# NMEA0183Breakout-ISO-4_3.net
KiCad netlist of a schematic drawn in EAGLE
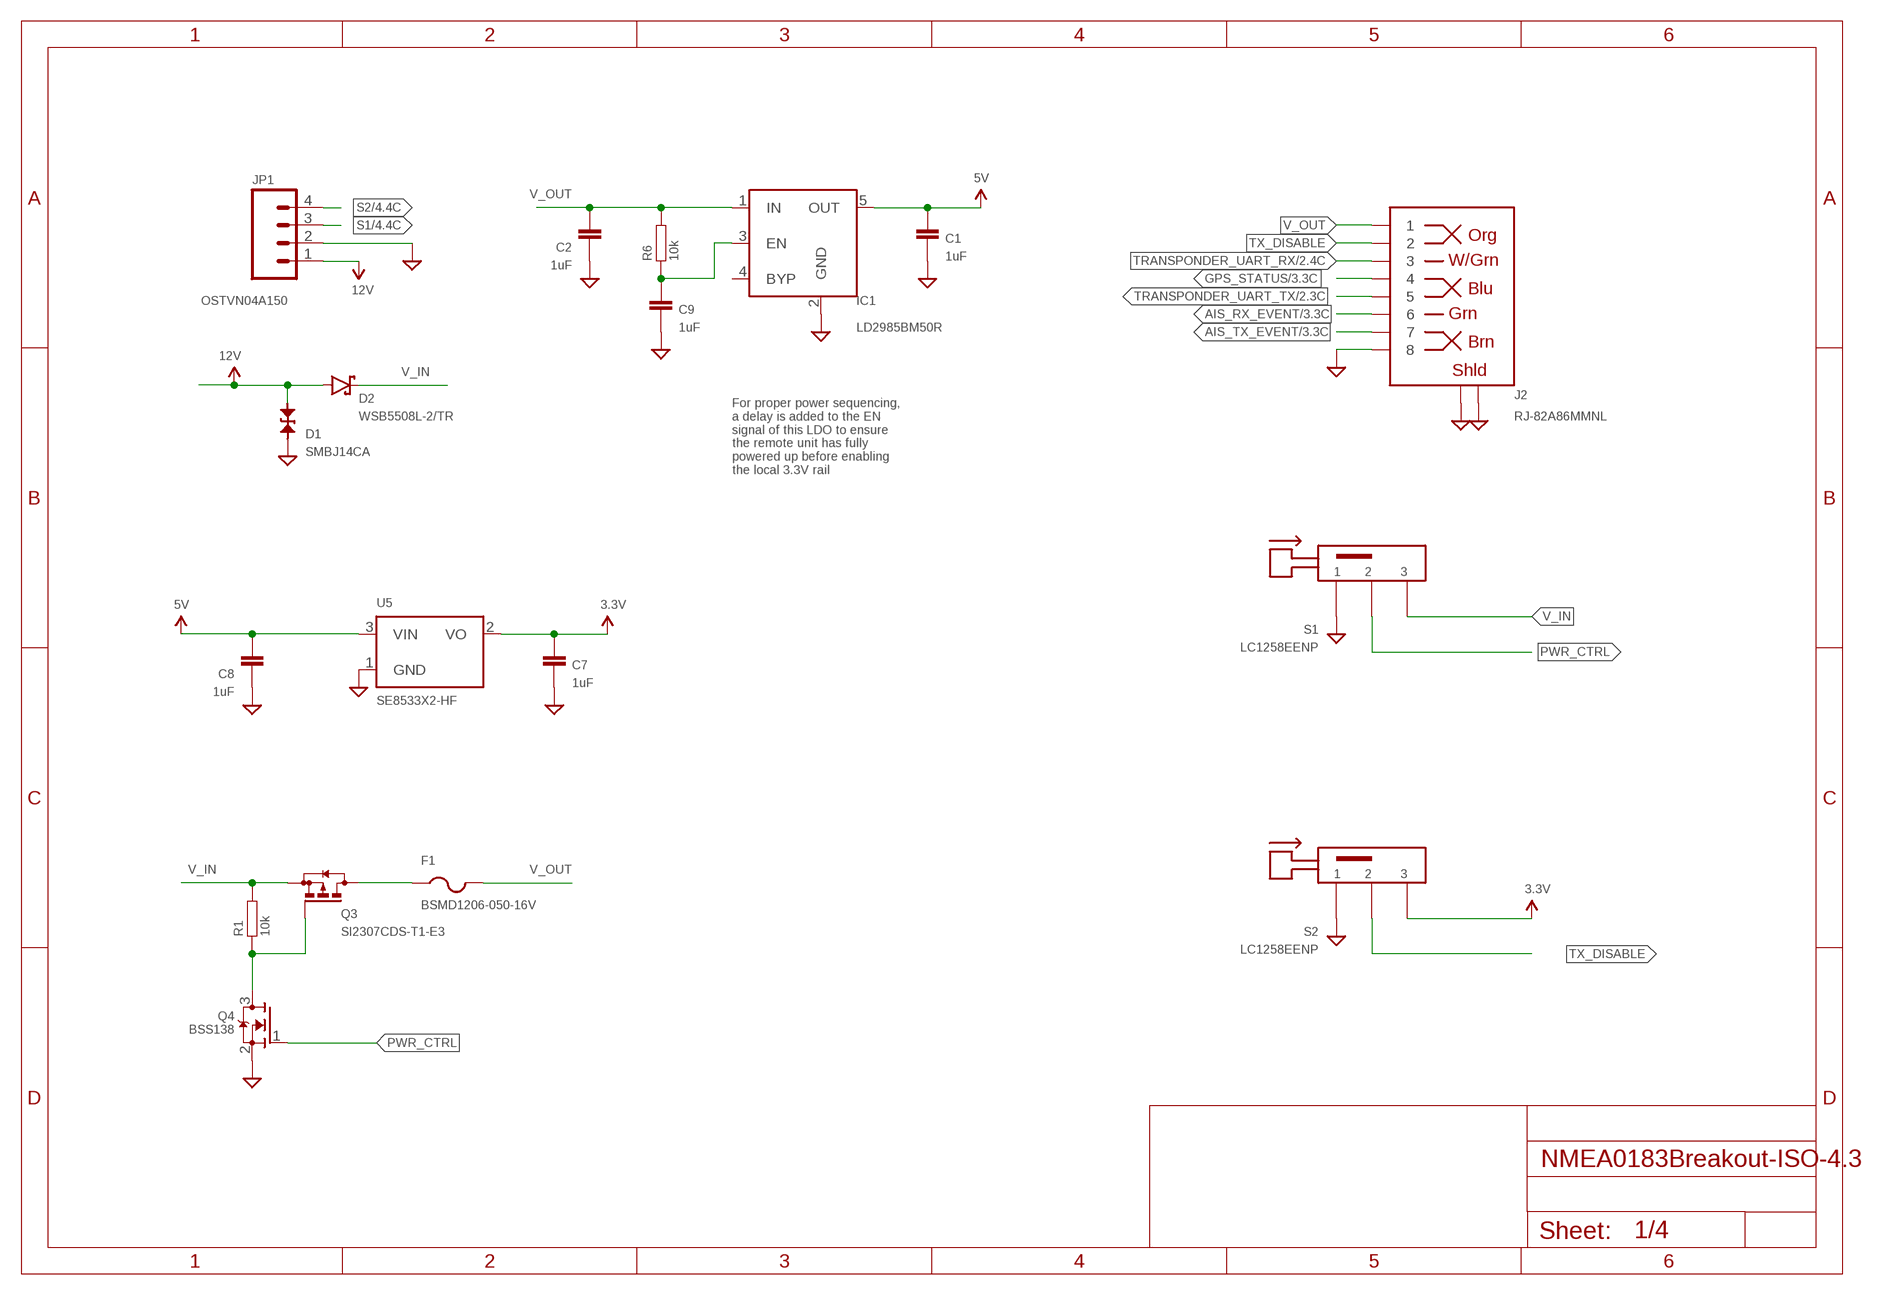
[diagram p0: schematic, sheet 1]
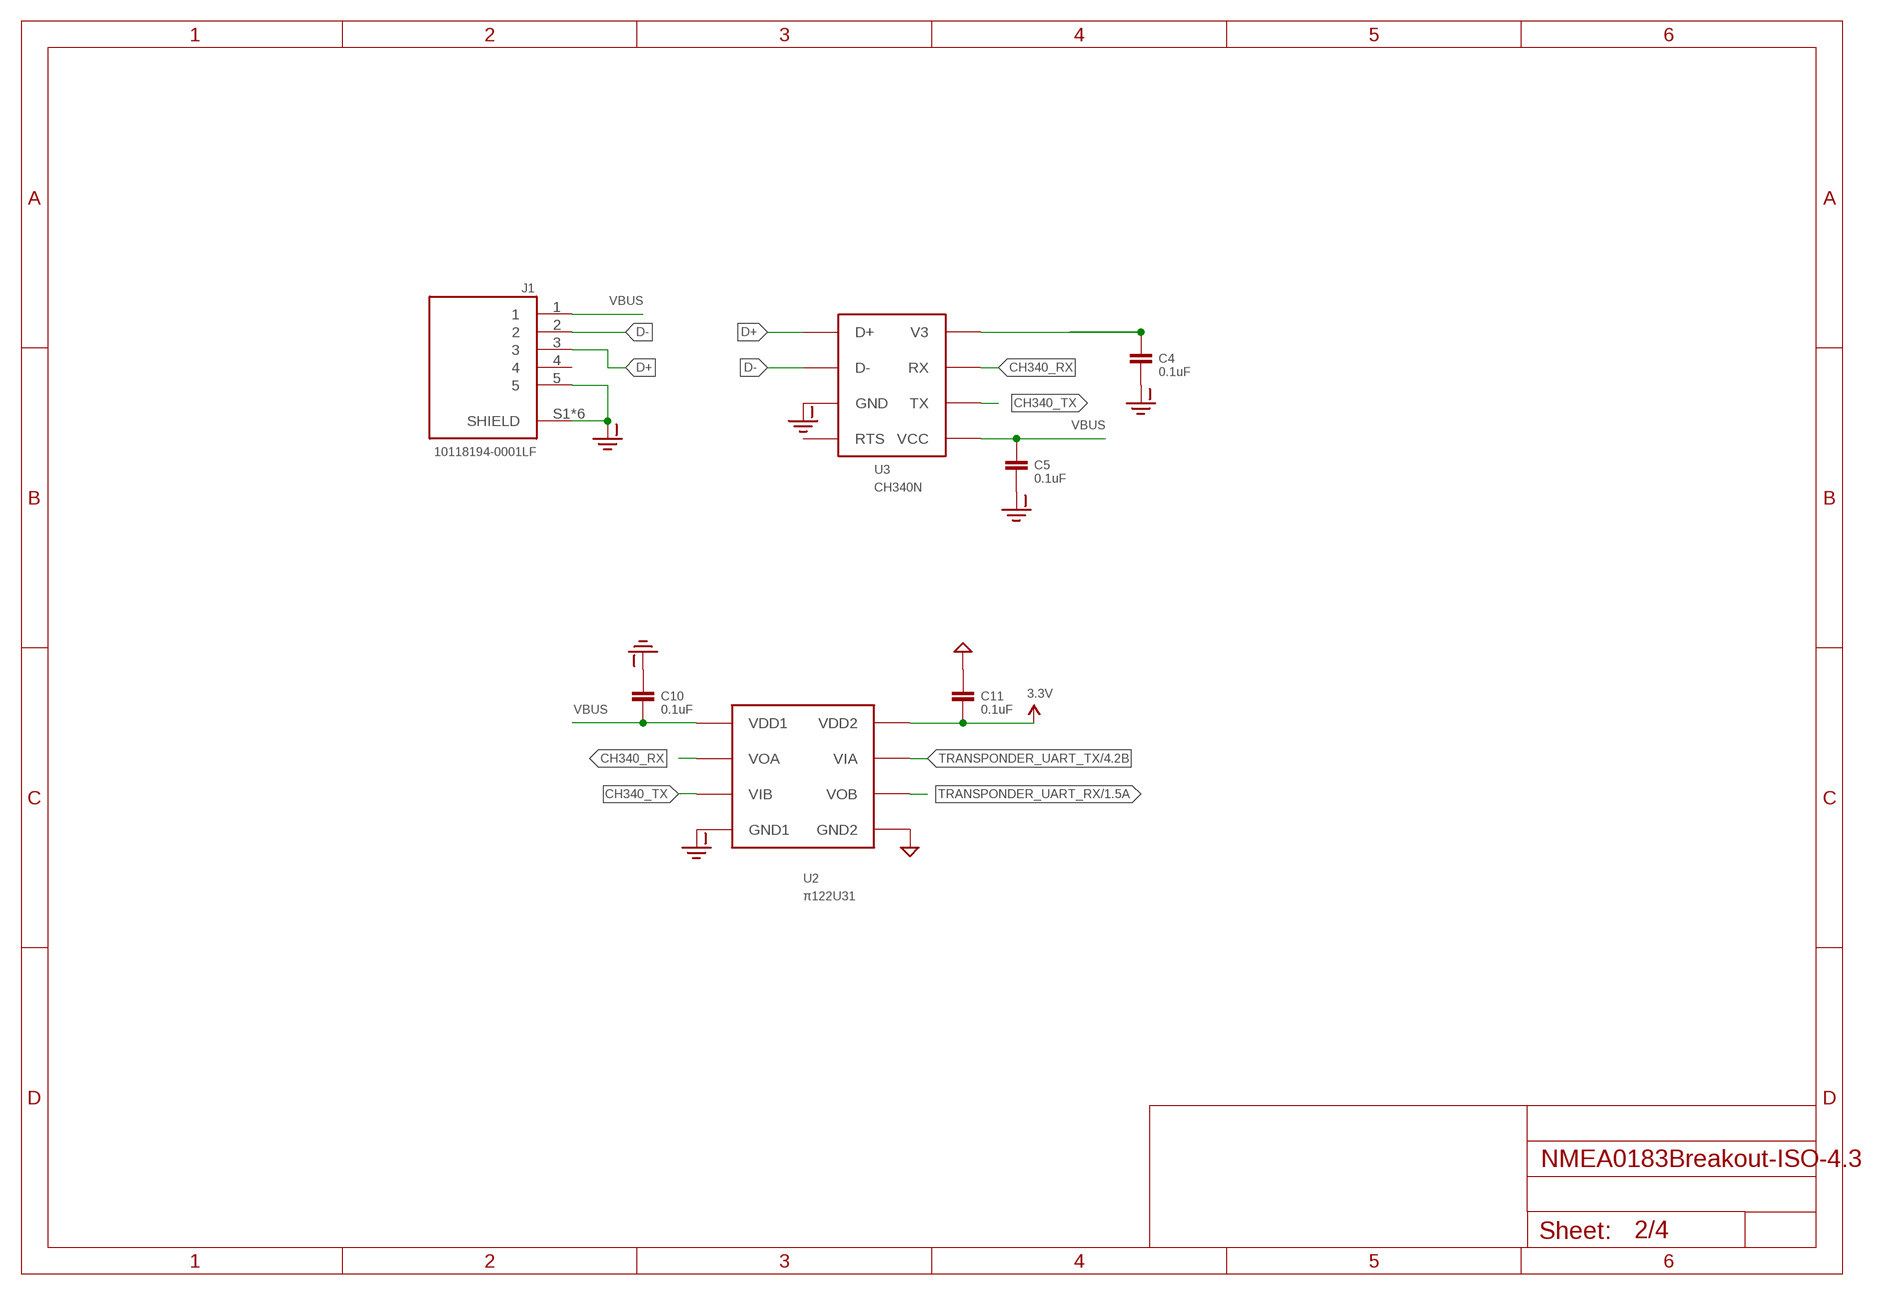
[diagram p1: schematic, sheet 2]
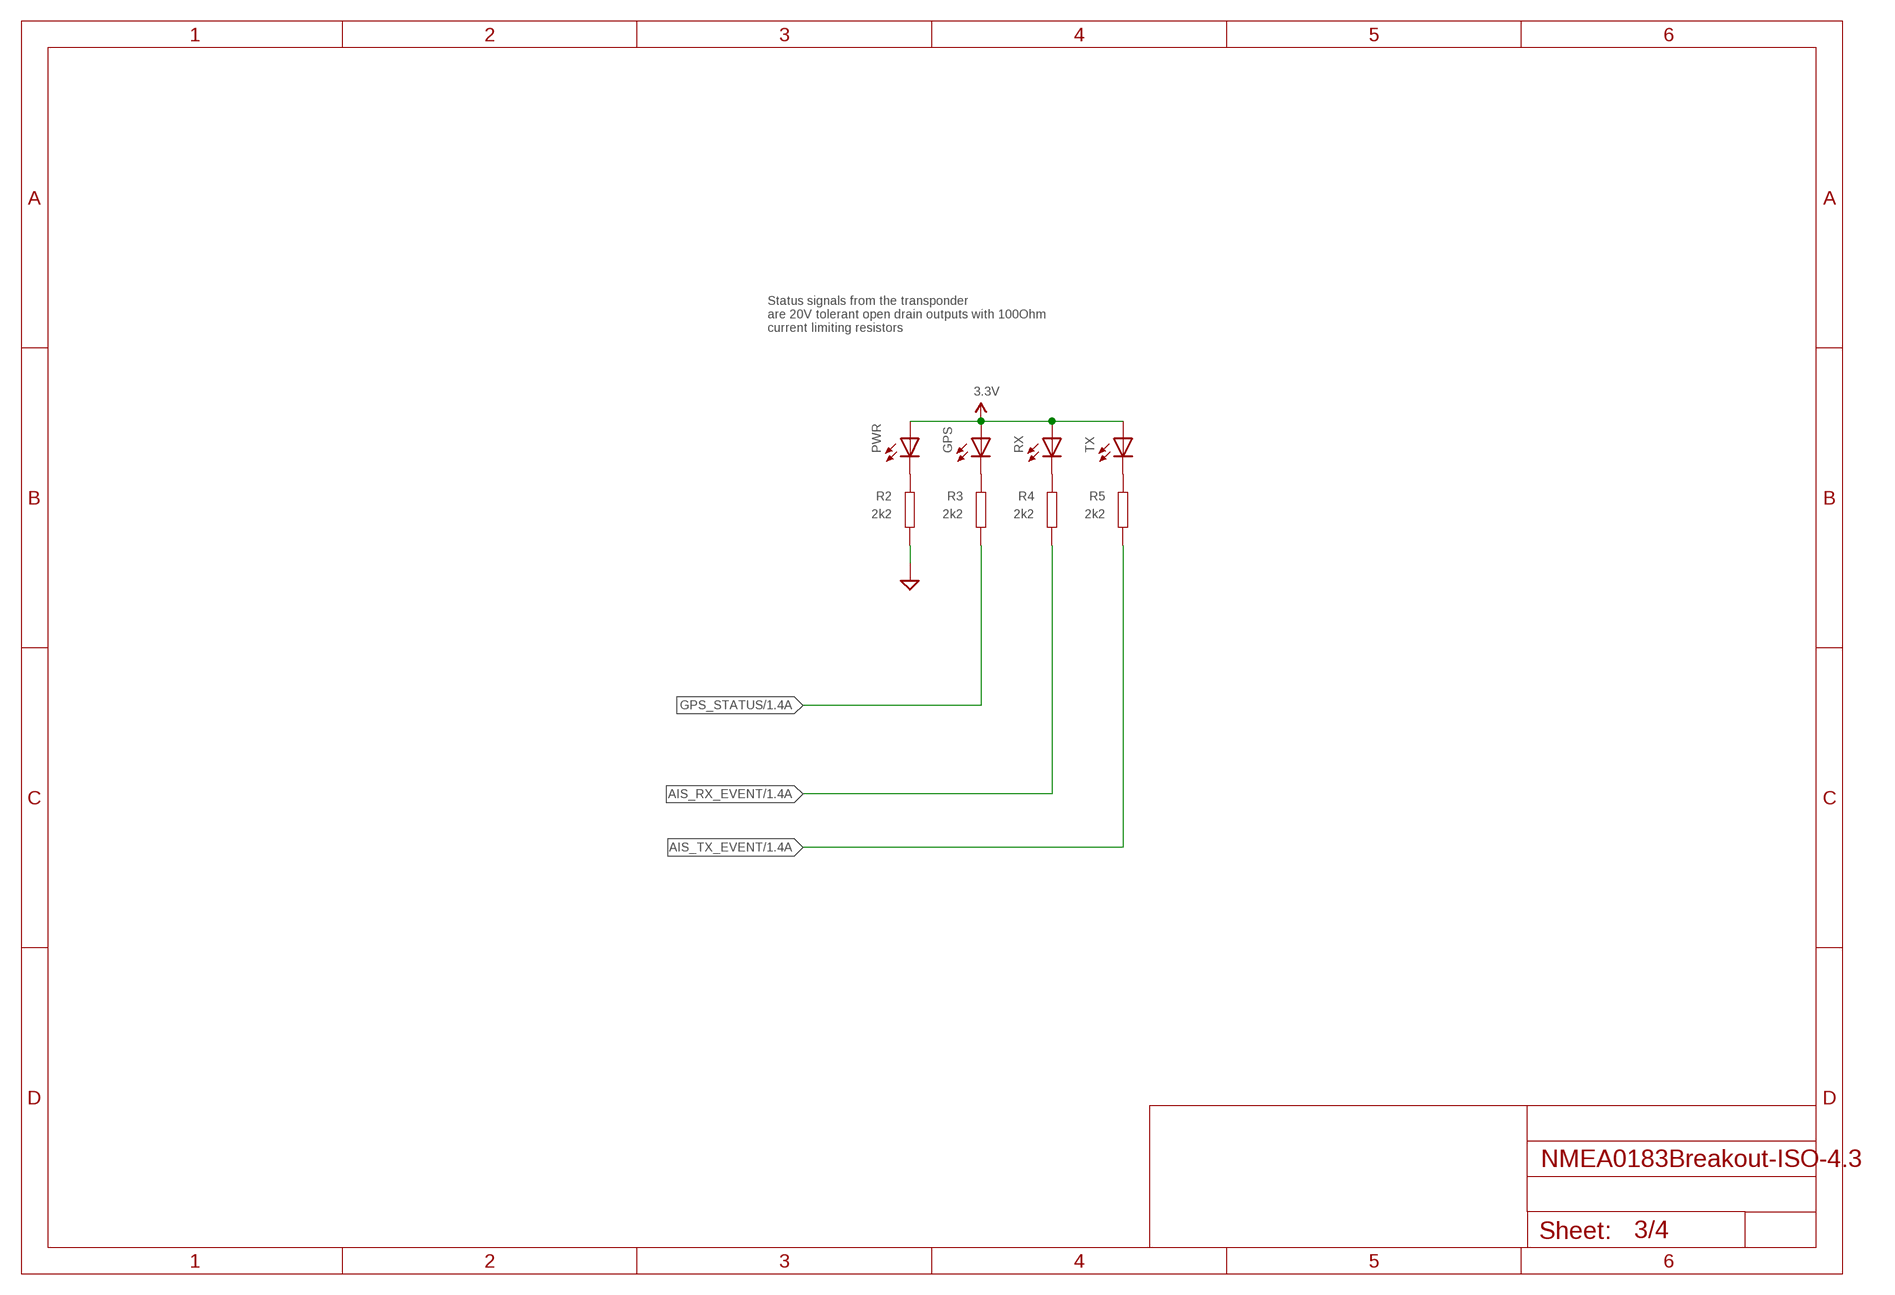
[diagram p2: schematic, sheet 3]
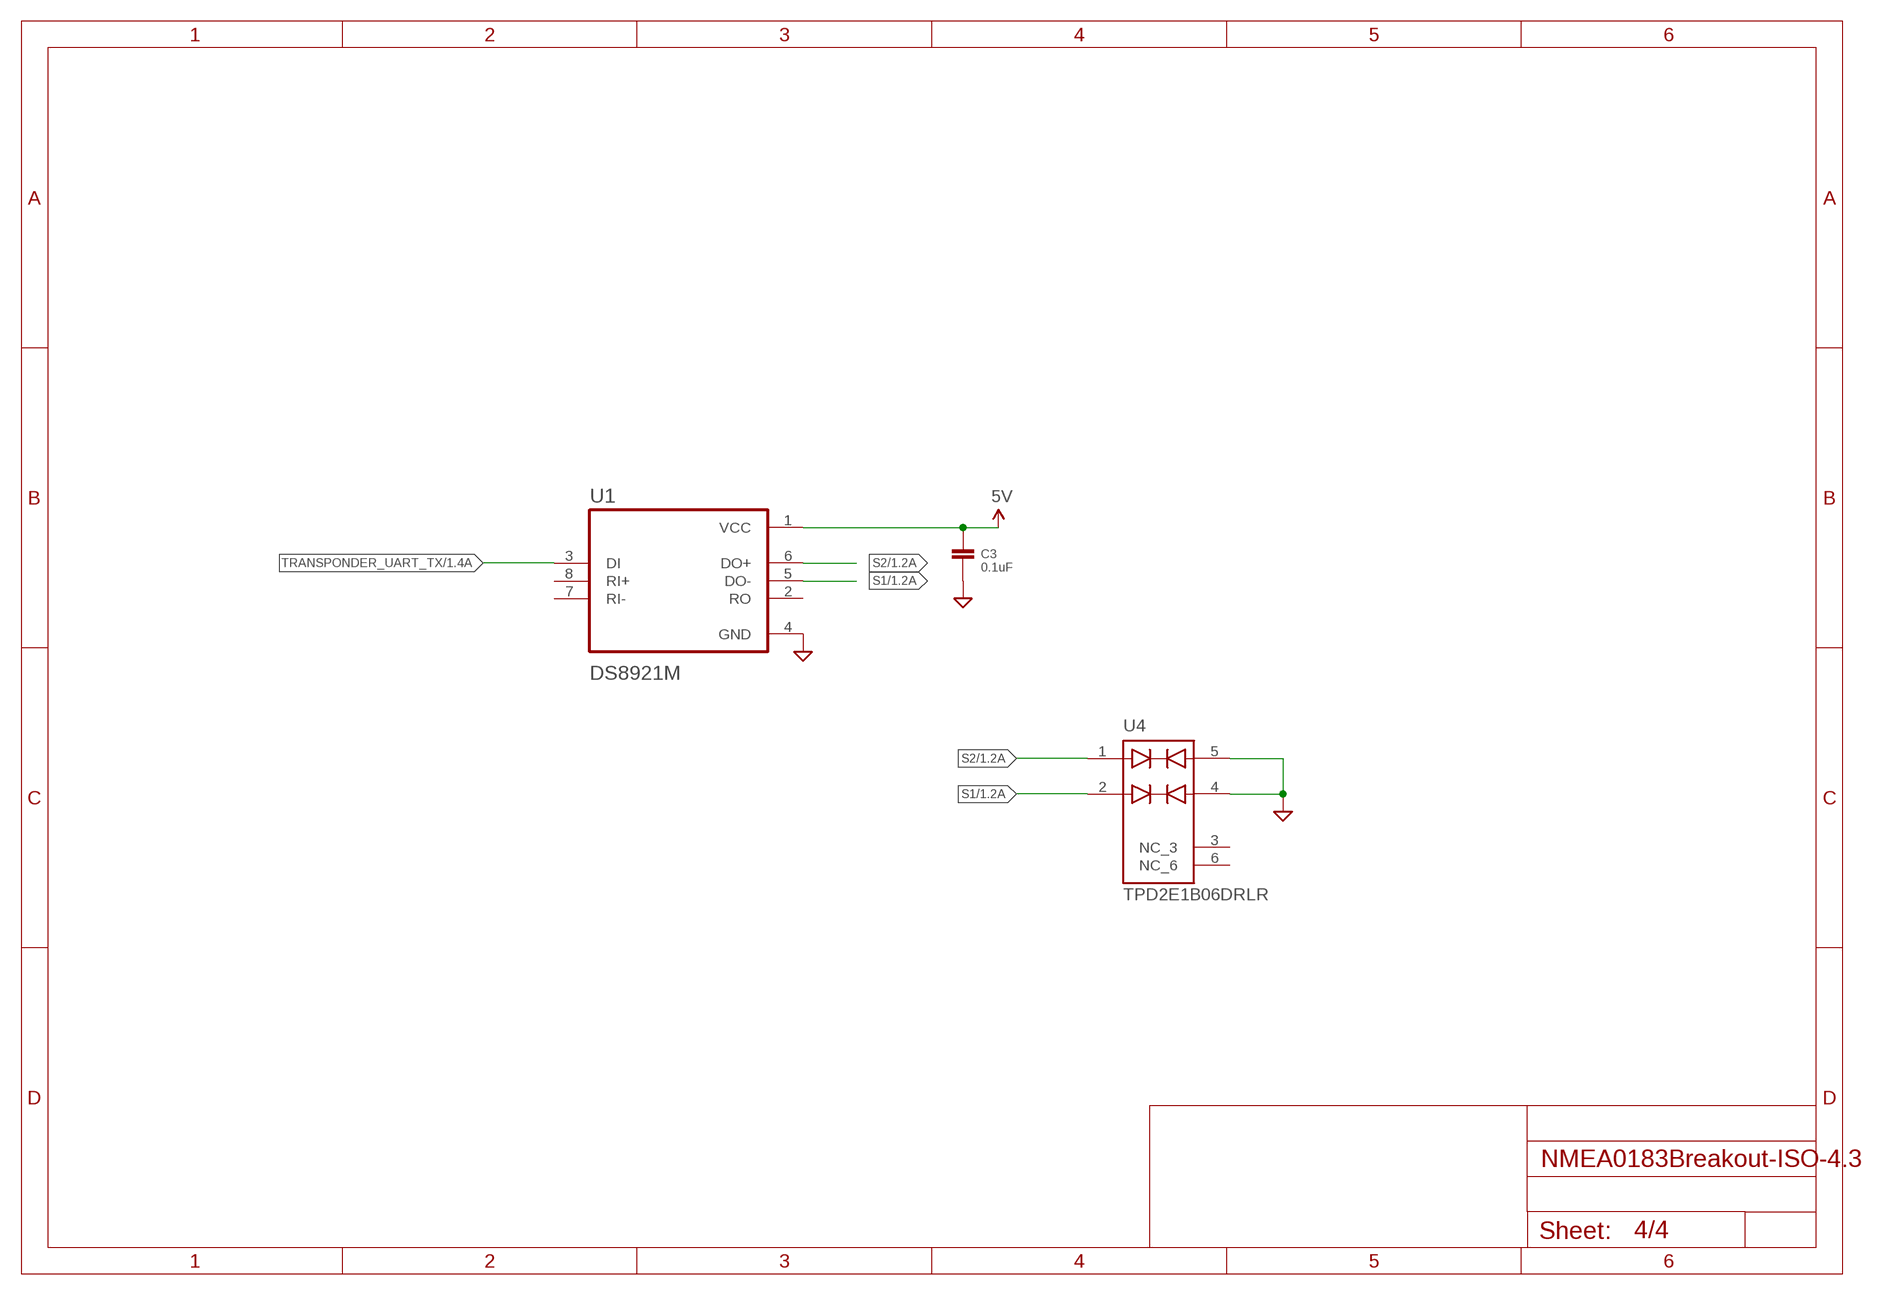
[diagram p3: schematic, sheet 4]

(export (version "E")
  (design (tool "Eeschema 10.0.6"))
  (components
    (comp (ref "C1")
      (value "1uF")
      (footprint "eagle-import:0603")
      (fields (field (name "PARTNO") "CC0603KRX5R8BB105"))
      (libsource (lib "eagle-import") (part "CAPACITOR0603"))
    )
    (comp (ref "C2")
      (value "1uF")
      (footprint "eagle-import:0603")
      (fields (field (name "PARTNO") "CC0603KRX5R8BB105"))
      (libsource (lib "eagle-import") (part "CAPACITOR0603"))
    )
    (comp (ref "C7")
      (value "1uF")
      (footprint "eagle-import:0603")
      (fields (field (name "PARTNO") "CC0603KRX5R8BB105"))
      (libsource (lib "eagle-import") (part "CAPACITOR0603"))
    )
    (comp (ref "C8")
      (value "1uF")
      (footprint "eagle-import:0603")
      (fields (field (name "PARTNO") "CC0603KRX5R8BB105"))
      (libsource (lib "eagle-import") (part "CAPACITOR0603"))
    )
    (comp (ref "C9")
      (value "1uF")
      (footprint "eagle-import:0603")
      (fields (field (name "PARTNO") "CC0603KRX5R8BB105"))
      (libsource (lib "eagle-import") (part "CAPACITOR0603"))
    )
    (comp (ref "D1")
      (value "SMBJ14CA")
      (footprint "eagle-import:SMB-BIDIR")
      (fields (field (name "PARTNO") "SMBJ14CA"))
      (libsource (lib "eagle-import") (part "DIODE-TVS-BIDIRSMB"))
    )
    (comp (ref "D2")
      (value "WSB5508L-2/TR")
      (footprint "eagle-import:SOD123")
      (fields (field (name "PARTNO") "WSB5508L-2/TR"))
      (libsource (lib "eagle-import") (part "DIODE-SCHOTTKYSOD123"))
    )
    (comp (ref "F1")
      (value "BSMD1206-050-16V")
      (footprint "eagle-import:R1206")
      (libsource (lib "eagle-import") (part "PTCFUSE-1206"))
    )
    (comp (ref "IC1")
      (value "LD2985BM50R")
      (footprint "eagle-import:SOT23-5")
      (libsource (lib "eagle-import") (part "MIC5219XX"))
    )
    (comp (ref "J2")
      (value "RJ-82A86MMNL")
      (footprint "eagle-import:RJ-82A86MMNL")
      (libsource (lib "eagle-import") (part "RJ-82A86MMNL"))
    )
    (comp (ref "JP1")
      (value "OSTVN04A150")
      (footprint "eagle-import:1X04")
      (libsource (lib "eagle-import") (part "M04PTH"))
    )
    (comp (ref "Q3")
      (value "SI2307CDS-T1-E3")
      (footprint "eagle-import:SOT23")
      (libsource (lib "eagle-import") (part "BSS84"))
    )
    (comp (ref "Q4")
      (value "BSS138")
      (footprint "eagle-import:SOT23")
      (libsource (lib "eagle-import") (part "MOSFET-NREFLOW"))
    )
    (comp (ref "R1")
      (value "10k")
      (footprint "eagle-import:0603")
      (fields (field (name "PARTNO") "RC0603FR-0710KL"))
      (libsource (lib "eagle-import") (part "RESISTOR0603"))
    )
    (comp (ref "R6")
      (value "10k")
      (footprint "eagle-import:0603")
      (fields (field (name "PARTNO") "RC0603FR-0710KL"))
      (libsource (lib "eagle-import") (part "RESISTOR0603"))
    )
    (comp (ref "S1")
      (value "LC1258EENP")
      (footprint "eagle-import:LC1258XXNP")
      (fields (field (name "PARTNO") "LC1258EENP"))
      (libsource (lib "eagle-import") (part "LC1258XXNP"))
    )
    (comp (ref "S2")
      (value "LC1258EENP")
      (footprint "eagle-import:LC1258XXNP")
      (fields (field (name "PARTNO") "LC1258EENP"))
      (libsource (lib "eagle-import") (part "LC1258XXNP"))
    )
    (comp (ref "U5")
      (value "SE8533X2-HF")
      (footprint "eagle-import:SOT23")
      (libsource (lib "eagle-import") (part "MCP1799T"))
    )
    (comp (ref "C4")
      (value "0.1uF")
      (footprint "eagle-import:0603")
      (fields (field (name "PARTNO") "06035C104KAT2A"))
      (libsource (lib "eagle-import") (part "CAPACITOR0603"))
    )
    (comp (ref "C5")
      (value "0.1uF")
      (footprint "eagle-import:0603")
      (fields (field (name "PARTNO") "06035C104KAT2A"))
      (libsource (lib "eagle-import") (part "CAPACITOR0603"))
    )
    (comp (ref "C10")
      (value "0.1uF")
      (footprint "eagle-import:0603")
      (fields (field (name "PARTNO") "06035C104KAT2A"))
      (libsource (lib "eagle-import") (part "CAPACITOR0603"))
    )
    (comp (ref "C11")
      (value "0.1uF")
      (footprint "eagle-import:0603")
      (fields (field (name "PARTNO") "06035C104KAT2A"))
      (libsource (lib "eagle-import") (part "CAPACITOR0603"))
    )
    (comp (ref "J1")
      (value "10118194-0001LF")
      (footprint "eagle-import:AMPHENOL_10118194-0001LF")
      (fields (field (name "MF") "Amphenol ICC (FCI)"))
      (libsource (lib "eagle-import") (part "10118194-0001LF"))
    )
    (comp (ref "U2")
      (value "π122U31")
      (footprint "eagle-import:SOIC8")
      (libsource (lib "eagle-import") (part "PI122U3X"))
    )
    (comp (ref "U3")
      (value "CH340N")
      (footprint "eagle-import:SOIC-8")
      (libsource (lib "eagle-import") (part "CH330N"))
    )
    (comp (ref "GPS")
      (value "LEDCHIPLED_1206")
      (footprint "eagle-import:CHIPLED_1206")
      (fields (field (name "PARTNO") "TJ-S3216CL9T5ALC2G-A5"))
      (libsource (lib "eagle-import") (part "LEDCHIPLED_1206"))
    )
    (comp (ref "PWR")
      (value "LEDCHIPLED_1206")
      (footprint "eagle-import:CHIPLED_1206")
      (fields (field (name "PARTNO") "TJ-S3216CL9T5ALC2G-A5"))
      (libsource (lib "eagle-import") (part "LEDCHIPLED_1206"))
    )
    (comp (ref "R2")
      (value "2k2")
      (footprint "eagle-import:0603")
      (fields (field (name "PARTNO") "CR0603-FX-2201ELF"))
      (libsource (lib "eagle-import") (part "RESISTOR0603"))
    )
    (comp (ref "R3")
      (value "2k2")
      (footprint "eagle-import:0603")
      (fields (field (name "PARTNO") "CR0603-FX-2201ELF"))
      (libsource (lib "eagle-import") (part "RESISTOR0603"))
    )
    (comp (ref "R4")
      (value "2k2")
      (footprint "eagle-import:0603")
      (fields (field (name "PARTNO") "CR0603-FX-2201ELF"))
      (libsource (lib "eagle-import") (part "RESISTOR0603"))
    )
    (comp (ref "R5")
      (value "2k2")
      (footprint "eagle-import:0603")
      (fields (field (name "PARTNO") "CR0603-FX-2201ELF"))
      (libsource (lib "eagle-import") (part "RESISTOR0603"))
    )
    (comp (ref "RX")
      (value "LEDCHIPLED_1206")
      (footprint "eagle-import:CHIPLED_1206")
      (fields (field (name "PARTNO") "TJ-S3216CL9T5ALC2G-A5"))
      (libsource (lib "eagle-import") (part "LEDCHIPLED_1206"))
    )
    (comp (ref "TX")
      (value "LEDCHIPLED_1206")
      (footprint "eagle-import:CHIPLED_1206")
      (fields (field (name "PARTNO") "TJ-S3216CL9T5ALC2G-A5"))
      (libsource (lib "eagle-import") (part "LEDCHIPLED_1206"))
    )
    (comp (ref "C3")
      (value "0.1uF")
      (footprint "eagle-import:0603")
      (fields (field (name "PARTNO") "06035C104KAT2A"))
      (libsource (lib "eagle-import") (part "CAPACITOR0603"))
    )
    (comp (ref "U1")
      (value "DS8921M")
      (footprint "eagle-import:SOIC127P599X175-8N")
      (fields (field (name "MF") "Texas Instruments") (field (name "MP") "DS8921M/NOPB"))
      (libsource (lib "eagle-import") (part "DS8921M"))
    )
    (comp (ref "U4")
      (value "TPD2E1B06DRLR")
      (footprint "eagle-import:SOTFL50P160X60-6N")
      (fields (field (name "MF") "Texas Instruments"))
      (libsource (lib "eagle-import") (part "TPD2E1B06DRLR"))
    )
  )
  (nets
    (net (code "1") (name "3.3V") (class "Default")
      (node (ref "C11") (pin "P$2") (pinfunction "2_P$2") (pintype "passive"))
      (node (ref "C7") (pin "P$1") (pinfunction "1_P$1") (pintype "passive"))
      (node (ref "GPS") (pin "A") (pinfunction "A_A") (pintype "passive"))
      (node (ref "PWR") (pin "A") (pinfunction "A_A") (pintype "passive"))
      (node (ref "RX") (pin "A") (pinfunction "A_A") (pintype "passive"))
      (node (ref "S2") (pin "P$3") (pinfunction "3_P$3") (pintype "bidirectional"))
      (node (ref "TX") (pin "A") (pinfunction "A_A") (pintype "passive"))
      (node (ref "U2") (pin "8") (pinfunction "VDD2_8") (pintype "bidirectional"))
      (node (ref "U5") (pin "2") (pinfunction "VO_2") (pintype "output"))
    )
    (net (code "2") (name "5V") (class "Default")
      (node (ref "C1") (pin "P$1") (pinfunction "1_P$1") (pintype "passive"))
      (node (ref "C3") (pin "P$1") (pinfunction "1_P$1") (pintype "passive"))
      (node (ref "C8") (pin "P$1") (pinfunction "1_P$1") (pintype "passive"))
      (node (ref "IC1") (pin "5") (pinfunction "OUT_5") (pintype "output"))
      (node (ref "U1") (pin "1") (pinfunction "VCC_1") (pintype "power_in"))
      (node (ref "U5") (pin "3") (pinfunction "VIN_3") (pintype "input"))
    )
    (net (code "3") (name "12V") (class "Default")
      (node (ref "D1") (pin "A") (pinfunction "P$1_A") (pintype "bidirectional"))
      (node (ref "D2") (pin "A") (pinfunction "A_A") (pintype "passive"))
      (node (ref "JP1") (pin "1") (pinfunction "1_1") (pintype "passive"))
    )
    (net (code "4") (name "AIS_RX_EVENT") (class "Default")
      (node (ref "J2") (pin "P$6") (pinfunction "6_P$6") (pintype "bidirectional"))
      (node (ref "R4") (pin "P$2") (pinfunction "P$2_P$2") (pintype "passive"))
    )
    (net (code "5") (name "AIS_TX_EVENT") (class "Default")
      (node (ref "J2") (pin "P$7") (pinfunction "7_P$7") (pintype "bidirectional"))
      (node (ref "R5") (pin "P$2") (pinfunction "P$2_P$2") (pintype "passive"))
    )
    (net (code "6") (name "CH340_RX") (class "Default")
      (node (ref "U2") (pin "2") (pinfunction "VOA_2") (pintype "bidirectional"))
      (node (ref "U3") (pin "7") (pinfunction "RX_7") (pintype "bidirectional"))
    )
    (net (code "7") (name "CH340_TX") (class "Default")
      (node (ref "U2") (pin "3") (pinfunction "VIB_3") (pintype "bidirectional"))
      (node (ref "U3") (pin "6") (pinfunction "TX_6") (pintype "bidirectional"))
    )
    (net (code "8") (name "D+") (class "Default")
      (node (ref "J1") (pin "3") (pinfunction "3_3") (pintype "passive"))
      (node (ref "U3") (pin "1") (pinfunction "D+_1") (pintype "bidirectional"))
    )
    (net (code "9") (name "D-") (class "Default")
      (node (ref "J1") (pin "2") (pinfunction "2_2") (pintype "passive"))
      (node (ref "U3") (pin "2") (pinfunction "D-_2") (pintype "bidirectional"))
    )
    (net (code "10") (name "GND") (class "Default")
      (node (ref "C1") (pin "P$2") (pinfunction "2_P$2") (pintype "passive"))
      (node (ref "C11") (pin "P$1") (pinfunction "1_P$1") (pintype "passive"))
      (node (ref "C2") (pin "P$2") (pinfunction "2_P$2") (pintype "passive"))
      (node (ref "C3") (pin "P$2") (pinfunction "2_P$2") (pintype "passive"))
      (node (ref "C7") (pin "P$2") (pinfunction "2_P$2") (pintype "passive"))
      (node (ref "C8") (pin "P$2") (pinfunction "2_P$2") (pintype "passive"))
      (node (ref "C9") (pin "P$2") (pinfunction "2_P$2") (pintype "passive"))
      (node (ref "D1") (pin "C") (pinfunction "P$2_C") (pintype "bidirectional"))
      (node (ref "IC1") (pin "2") (pinfunction "GND_2") (pintype "power_in"))
      (node (ref "J2") (pin "P$10") (pinfunction "SHLD_P$10") (pintype "bidirectional"))
      (node (ref "J2") (pin "P$11") (pinfunction "SHLD_P$11") (pintype "bidirectional"))
      (node (ref "J2") (pin "P$12") (pinfunction "SHLD_P$12") (pintype "bidirectional"))
      (node (ref "J2") (pin "P$8") (pinfunction "8_P$8") (pintype "bidirectional"))
      (node (ref "J2") (pin "P$9") (pinfunction "SHLD_P$9") (pintype "bidirectional"))
      (node (ref "JP1") (pin "2") (pinfunction "2_2") (pintype "passive"))
      (node (ref "Q4") (pin "2") (pinfunction "S_2") (pintype "bidirectional"))
      (node (ref "R2") (pin "P$2") (pinfunction "P$2_P$2") (pintype "passive"))
      (node (ref "S1") (pin "P$1") (pinfunction "1_P$1") (pintype "bidirectional"))
      (node (ref "S2") (pin "P$1") (pinfunction "1_P$1") (pintype "bidirectional"))
      (node (ref "U1") (pin "4") (pinfunction "GND_4") (pintype "power_in"))
      (node (ref "U2") (pin "5") (pinfunction "GND2_5") (pintype "bidirectional"))
      (node (ref "U4") (pin "4") (pinfunction "IOB2_4") (pintype "bidirectional"))
      (node (ref "U4") (pin "5") (pinfunction "IOA2_5") (pintype "bidirectional"))
      (node (ref "U5") (pin "1") (pinfunction "GND_1") (pintype "passive"))
    )
    (net (code "11") (name "GND-ISO") (class "Default")
      (node (ref "C10") (pin "P$1") (pinfunction "1_P$1") (pintype "passive"))
      (node (ref "C4") (pin "P$2") (pinfunction "2_P$2") (pintype "passive"))
      (node (ref "C5") (pin "P$2") (pinfunction "2_P$2") (pintype "passive"))
      (node (ref "J1") (pin "5") (pinfunction "5_5") (pintype "passive"))
      (node (ref "J1") (pin "S1") (pinfunction "SHIELD_S1") (pintype "passive"))
      (node (ref "J1") (pin "S2") (pinfunction "SHIELD_S2") (pintype "passive"))
      (node (ref "J1") (pin "S3") (pinfunction "SHIELD_S3") (pintype "passive"))
      (node (ref "J1") (pin "S4") (pinfunction "SHIELD_S4") (pintype "passive"))
      (node (ref "J1") (pin "S5") (pinfunction "SHIELD_S5") (pintype "passive"))
      (node (ref "J1") (pin "S6") (pinfunction "SHIELD_S6") (pintype "passive"))
      (node (ref "U2") (pin "4") (pinfunction "GND1_4") (pintype "bidirectional"))
      (node (ref "U3") (pin "3") (pinfunction "GND_3") (pintype "bidirectional"))
    )
    (net (code "12") (name "GPS_STATUS") (class "Default")
      (node (ref "J2") (pin "P$4") (pinfunction "4_P$4") (pintype "bidirectional"))
      (node (ref "R3") (pin "P$2") (pinfunction "P$2_P$2") (pintype "passive"))
    )
    (net (code "13") (name "Net-(C4-1)") (class "Default")
      (node (ref "C4") (pin "P$1") (pinfunction "1_P$1") (pintype "passive"))
      (node (ref "U3") (pin "8") (pinfunction "V3_8") (pintype "bidirectional"))
    )
    (net (code "14") (name "Net-(C9-1)") (class "Default")
      (node (ref "C9") (pin "P$1") (pinfunction "1_P$1") (pintype "passive"))
      (node (ref "IC1") (pin "3") (pinfunction "EN_3") (pintype "input"))
      (node (ref "R6") (pin "P$1") (pinfunction "P$1_P$1") (pintype "passive"))
    )
    (net (code "15") (name "Net-(GPS-PadC)") (class "Default")
      (node (ref "GPS") (pin "C") (pinfunction "C_C") (pintype "passive"))
      (node (ref "R3") (pin "P$1") (pinfunction "P$1_P$1") (pintype "passive"))
    )
    (net (code "16") (name "Net-(PWR-PadC)") (class "Default")
      (node (ref "PWR") (pin "C") (pinfunction "C_C") (pintype "passive"))
      (node (ref "R2") (pin "P$1") (pinfunction "P$1_P$1") (pintype "passive"))
    )
    (net (code "17") (name "Net-(Q3-D)") (class "Default")
      (node (ref "F1") (pin "1") (pinfunction "1_1") (pintype "passive"))
      (node (ref "Q3") (pin "3") (pinfunction "D_3") (pintype "passive"))
    )
    (net (code "18") (name "Net-(Q3-G)") (class "Default")
      (node (ref "Q3") (pin "1") (pinfunction "G_1") (pintype "passive"))
      (node (ref "Q4") (pin "3") (pinfunction "D_3") (pintype "bidirectional"))
      (node (ref "R1") (pin "P$1") (pinfunction "P$1_P$1") (pintype "passive"))
    )
    (net (code "19") (name "Net-(R4-PadP$1)") (class "Default")
      (node (ref "R4") (pin "P$1") (pinfunction "P$1_P$1") (pintype "passive"))
      (node (ref "RX") (pin "C") (pinfunction "C_C") (pintype "passive"))
    )
    (net (code "20") (name "Net-(R5-PadP$1)") (class "Default")
      (node (ref "R5") (pin "P$1") (pinfunction "P$1_P$1") (pintype "passive"))
      (node (ref "TX") (pin "C") (pinfunction "C_C") (pintype "passive"))
    )
    (net (code "21") (name "PWR_CTRL") (class "Default")
      (node (ref "Q4") (pin "1") (pinfunction "G_1") (pintype "bidirectional"))
      (node (ref "S1") (pin "P$2") (pinfunction "2_P$2") (pintype "bidirectional"))
    )
    (net (code "22") (name "S1") (class "Default")
      (node (ref "JP1") (pin "3") (pinfunction "3_3") (pintype "passive"))
      (node (ref "U1") (pin "5") (pinfunction "DO-_5") (pintype "output"))
      (node (ref "U4") (pin "2") (pinfunction "IOB1_2") (pintype "bidirectional"))
    )
    (net (code "23") (name "S2") (class "Default")
      (node (ref "JP1") (pin "4") (pinfunction "4_4") (pintype "passive"))
      (node (ref "U1") (pin "6") (pinfunction "DO+_6") (pintype "output"))
      (node (ref "U4") (pin "1") (pinfunction "IOA1_1") (pintype "bidirectional"))
    )
    (net (code "24") (name "TRANSPONDER_UART_RX") (class "Default")
      (node (ref "J2") (pin "P$3") (pinfunction "3_P$3") (pintype "bidirectional"))
      (node (ref "U2") (pin "6") (pinfunction "VOB_6") (pintype "bidirectional"))
    )
    (net (code "25") (name "TRANSPONDER_UART_TX") (class "Default")
      (node (ref "J2") (pin "P$5") (pinfunction "5_P$5") (pintype "bidirectional"))
      (node (ref "U1") (pin "3") (pinfunction "DI_3") (pintype "input"))
      (node (ref "U2") (pin "7") (pinfunction "VIA_7") (pintype "bidirectional"))
    )
    (net (code "26") (name "TX_DISABLE") (class "Default")
      (node (ref "J2") (pin "P$2") (pinfunction "2_P$2") (pintype "bidirectional"))
      (node (ref "S2") (pin "P$2") (pinfunction "2_P$2") (pintype "bidirectional"))
    )
    (net (code "27") (name "VBUS") (class "Default")
      (node (ref "C10") (pin "P$2") (pinfunction "2_P$2") (pintype "passive"))
      (node (ref "C5") (pin "P$1") (pinfunction "1_P$1") (pintype "passive"))
      (node (ref "J1") (pin "1") (pinfunction "1_1") (pintype "passive"))
      (node (ref "U2") (pin "1") (pinfunction "VDD1_1") (pintype "bidirectional"))
      (node (ref "U3") (pin "5") (pinfunction "VCC_5") (pintype "bidirectional"))
    )
    (net (code "28") (name "V_IN") (class "Default")
      (node (ref "D2") (pin "C") (pinfunction "C_C") (pintype "passive"))
      (node (ref "Q3") (pin "2") (pinfunction "S_2") (pintype "passive"))
      (node (ref "R1") (pin "P$2") (pinfunction "P$2_P$2") (pintype "passive"))
      (node (ref "S1") (pin "P$3") (pinfunction "3_P$3") (pintype "bidirectional"))
    )
    (net (code "29") (name "V_OUT") (class "Default")
      (node (ref "C2") (pin "P$1") (pinfunction "1_P$1") (pintype "passive"))
      (node (ref "F1") (pin "2") (pinfunction "2_2") (pintype "passive"))
      (node (ref "IC1") (pin "1") (pinfunction "IN_1") (pintype "input"))
      (node (ref "J2") (pin "P$1") (pinfunction "1_P$1") (pintype "bidirectional"))
      (node (ref "R6") (pin "P$2") (pinfunction "P$2_P$2") (pintype "passive"))
    )
    (net (code "30") (name "unconnected-(IC1-BYP-Pad4)") (class "Default")
      (node (ref "IC1") (pin "4") (pinfunction "BYP_4") (pintype "passive"))
    )
    (net (code "31") (name "unconnected-(J1-Pad4)") (class "Default")
      (node (ref "J1") (pin "4") (pinfunction "4_4") (pintype "passive"))
    )
    (net (code "32") (name "unconnected-(U1-RI+-Pad8)") (class "Default")
      (node (ref "U1") (pin "8") (pinfunction "RI+_8") (pintype "input"))
    )
    (net (code "33") (name "unconnected-(U1-RI--Pad7)") (class "Default")
      (node (ref "U1") (pin "7") (pinfunction "RI-_7") (pintype "input"))
    )
    (net (code "34") (name "unconnected-(U1-RO-Pad2)") (class "Default")
      (node (ref "U1") (pin "2") (pinfunction "RO_2") (pintype "output"))
    )
    (net (code "35") (name "unconnected-(U3-RTS-Pad4)") (class "Default")
      (node (ref "U3") (pin "4") (pinfunction "RTS_4") (pintype "bidirectional"))
    )
    (net (code "36") (name "unconnected-(U4-NC_3-Pad3)") (class "Default")
      (node (ref "U4") (pin "3") (pinfunction "NC_3_3") (pintype "passive"))
    )
    (net (code "37") (name "unconnected-(U4-NC_6-Pad6)") (class "Default")
      (node (ref "U4") (pin "6") (pinfunction "NC_6_6") (pintype "passive"))
    )
  )
)
